# atmega128rf.net
KiCad netlist of a schematic drawn in Altium Designer
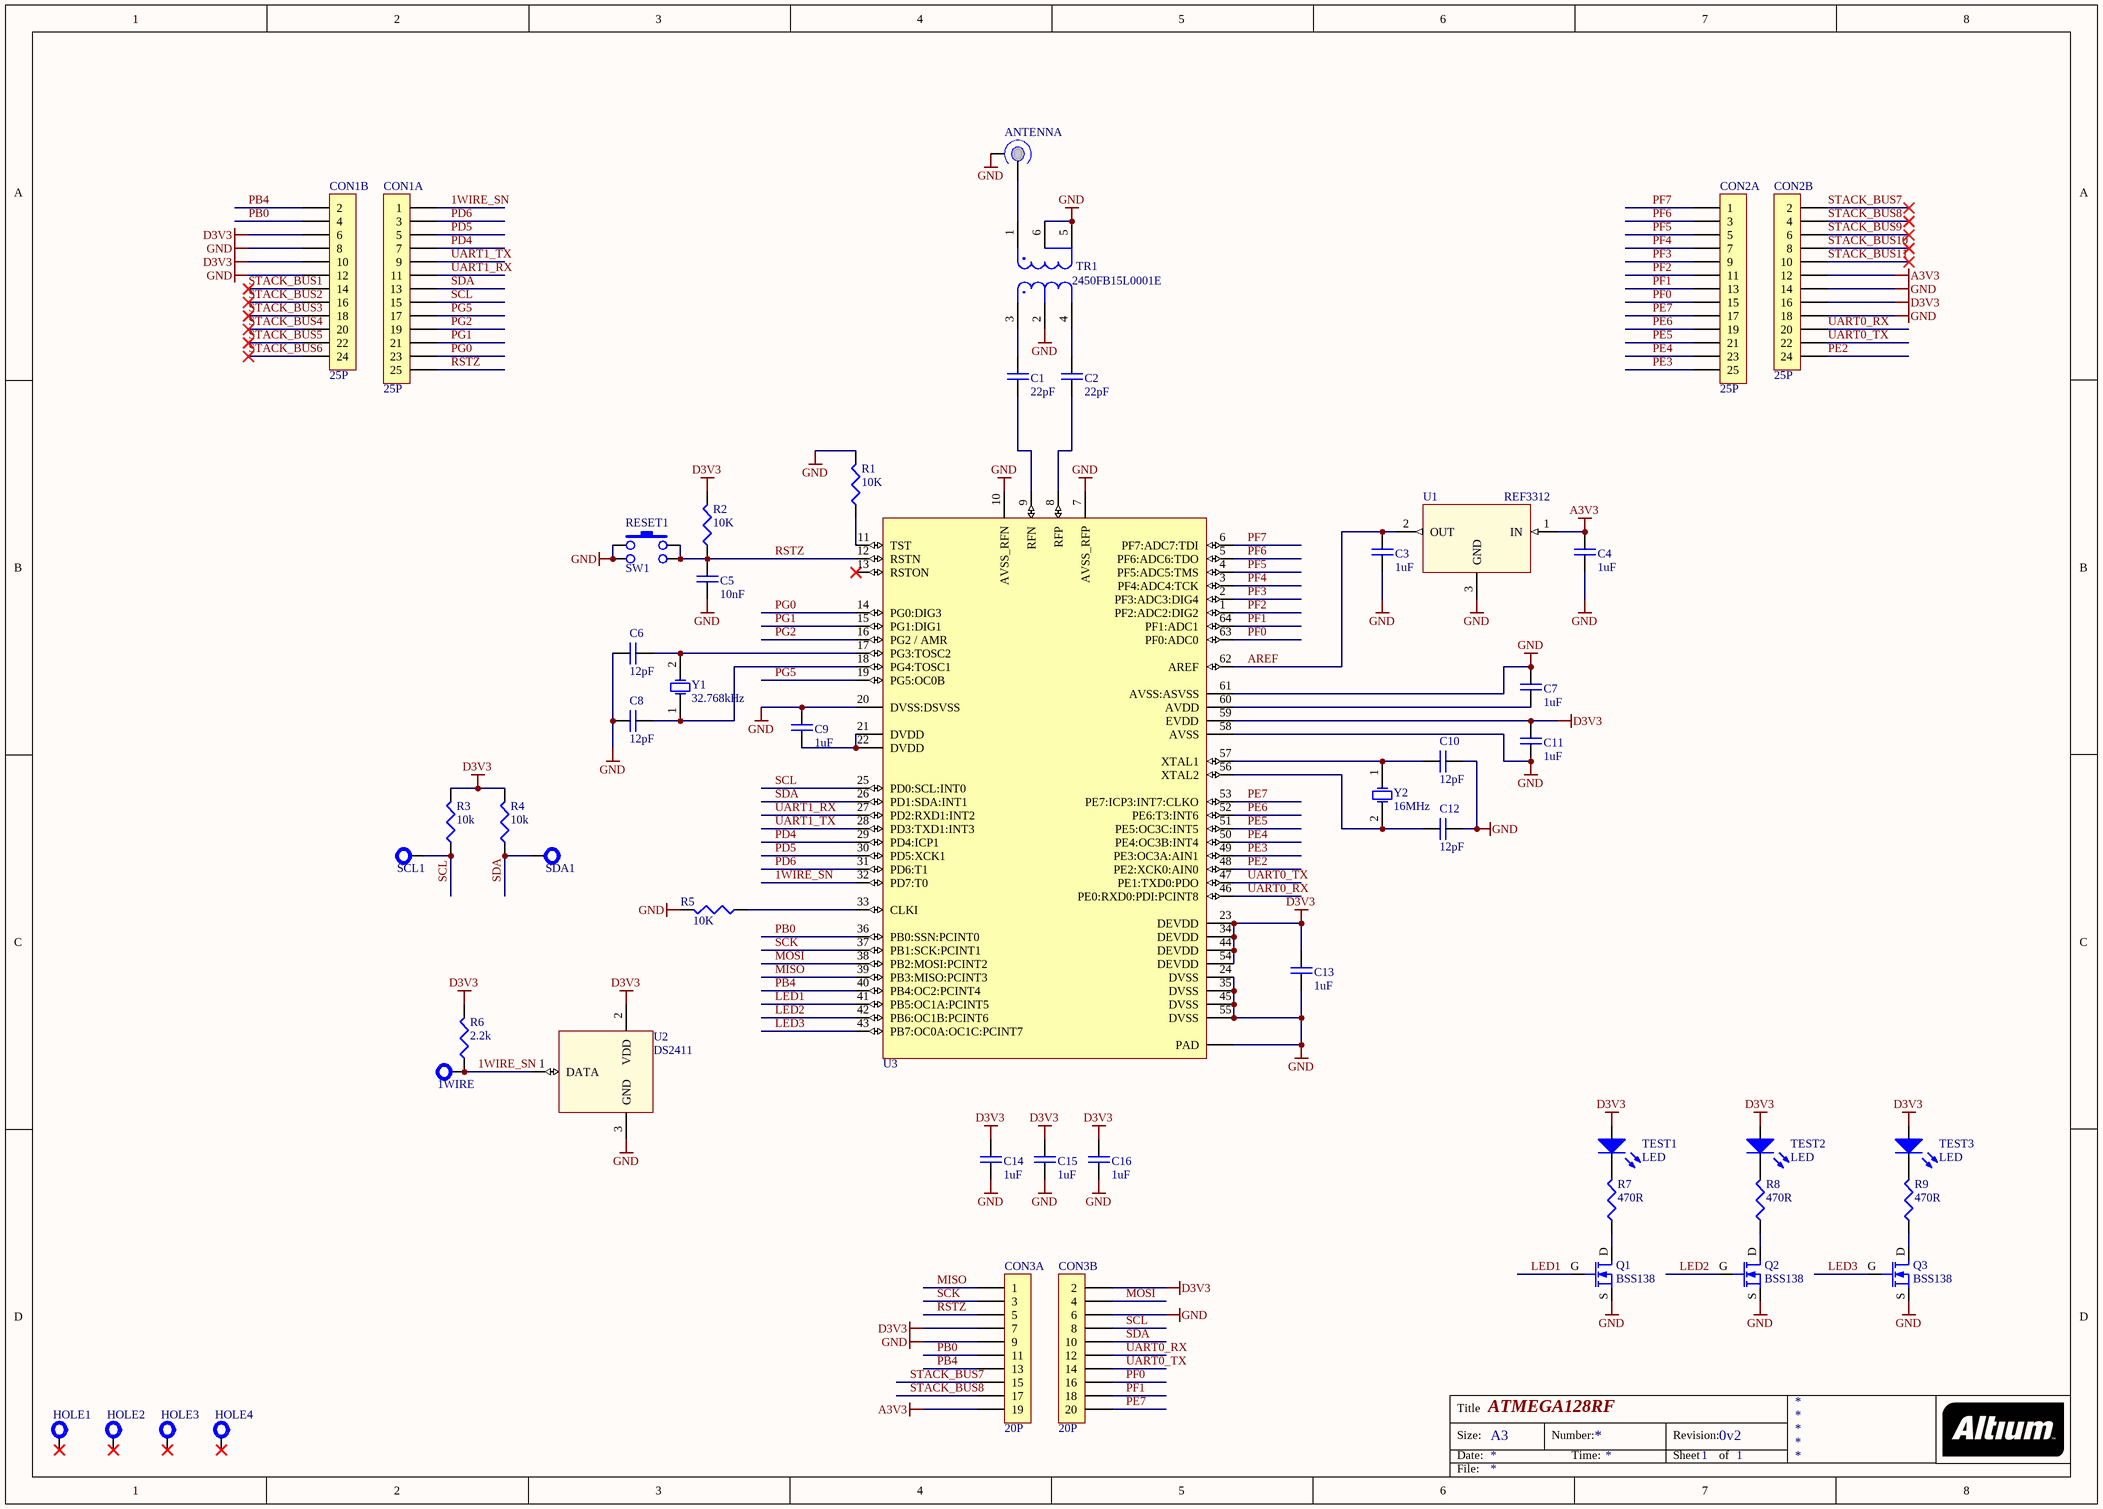
[diagram p0: atmega128rf.SchDoc]

(export (version "E")
  (design (tool "Eeschema 10.0.6"))
  (components
    (comp (ref "1WIRE")
      (value "Test Point")
      (footprint "TERMINAL")
      (description "Test/Probe Point")
      (fields (field (name "OWNER") "Nuno Brum"))
      (libsource (lib "Alcetronics_EM") (part "TEST-PROBE"))
    )
    (comp (ref "ANTENNA")
      (value "SMA")
      (footprint "SMA-JOHNSON-SCREW")
      (description "SMA to PCB - Coaxial connector")
      (fields (field (name "OWNER") "Nuno Brum"))
      (libsource (lib "Alcetronics_EM") (part "SMA"))
    )
    (comp (ref "C1")
      (value "22pF")
      (footprint "0402")
      (description "Capacitor")
      (fields (field (name "OWNER") "Nuno Brum"))
      (libsource (lib "Alcetronics_Devices") (part "CAP"))
    )
    (comp (ref "C2")
      (value "22pF")
      (footprint "0402")
      (description "Capacitor")
      (fields (field (name "OWNER") "Nuno Brum"))
      (libsource (lib "Alcetronics_Devices") (part "CAP"))
    )
    (comp (ref "C3")
      (value "1uF")
      (footprint "0603")
      (description "Capacitor")
      (fields (field (name "OWNER") "Nuno Brum"))
      (libsource (lib "Alcetronics_Devices") (part "CAP"))
    )
    (comp (ref "C4")
      (value "1uF")
      (footprint "0603")
      (description "Capacitor")
      (fields (field (name "OWNER") "Nuno Brum"))
      (libsource (lib "Alcetronics_Devices") (part "CAP"))
    )
    (comp (ref "C5")
      (value "10nF")
      (footprint "0603")
      (description "Capacitor")
      (fields (field (name "OWNER") "Nuno Brum"))
      (libsource (lib "Alcetronics_Devices") (part "CAP"))
    )
    (comp (ref "C6")
      (value "12pF")
      (footprint "0603")
      (description "Capacitor")
      (fields (field (name "OWNER") "Nuno Brum"))
      (libsource (lib "Alcetronics_Devices") (part "CAP"))
    )
    (comp (ref "C7")
      (value "1uF")
      (footprint "0603")
      (description "Capacitor")
      (fields (field (name "OWNER") "Nuno Brum"))
      (libsource (lib "Alcetronics_Devices") (part "CAP"))
    )
    (comp (ref "C8")
      (value "12pF")
      (footprint "0603")
      (description "Capacitor")
      (fields (field (name "OWNER") "Nuno Brum"))
      (libsource (lib "Alcetronics_Devices") (part "CAP"))
    )
    (comp (ref "C9")
      (value "1uF")
      (footprint "0603")
      (description "Capacitor")
      (fields (field (name "OWNER") "Nuno Brum"))
      (libsource (lib "Alcetronics_Devices") (part "CAP"))
    )
    (comp (ref "C10")
      (value "12pF")
      (footprint "0603")
      (description "Capacitor")
      (fields (field (name "OWNER") "Nuno Brum"))
      (libsource (lib "Alcetronics_Devices") (part "CAP"))
    )
    (comp (ref "C11")
      (value "1uF")
      (footprint "0603")
      (description "Capacitor")
      (fields (field (name "OWNER") "Nuno Brum"))
      (libsource (lib "Alcetronics_Devices") (part "CAP"))
    )
    (comp (ref "C12")
      (value "12pF")
      (footprint "0603")
      (description "Capacitor")
      (fields (field (name "OWNER") "Nuno Brum"))
      (libsource (lib "Alcetronics_Devices") (part "CAP"))
    )
    (comp (ref "C13")
      (value "1uF")
      (footprint "0603")
      (description "Capacitor")
      (fields (field (name "OWNER") "Nuno Brum"))
      (libsource (lib "Alcetronics_Devices") (part "CAP"))
    )
    (comp (ref "C14")
      (value "1uF")
      (footprint "0603")
      (description "Capacitor")
      (fields (field (name "OWNER") "Nuno Brum"))
      (libsource (lib "Alcetronics_Devices") (part "CAP"))
    )
    (comp (ref "C15")
      (value "1uF")
      (footprint "0603")
      (description "Capacitor")
      (fields (field (name "OWNER") "Nuno Brum"))
      (libsource (lib "Alcetronics_Devices") (part "CAP"))
    )
    (comp (ref "C16")
      (value "1uF")
      (footprint "0603")
      (description "Capacitor")
      (fields (field (name "OWNER") "Nuno Brum"))
      (libsource (lib "Alcetronics_Devices") (part "CAP"))
    )
    (comp (ref "CON1")
      (value "25P")
      (footprint "DF9-25-STACK")
      (description "Connector 25 Pins")
      (fields (field (name "OWNER") "Ricardo Rodrigues"))
      (libsource (lib "") (part "CON25_1"))
    )
    (comp (ref "CON2")
      (value "25P")
      (footprint "DF9-25-STACK")
      (description "Connector 25 Pins")
      (fields (field (name "OWNER") "Ricardo Rodrigues"))
      (libsource (lib "Alcetronics_EM") (part "CON25"))
    )
    (comp (ref "CON3")
      (value "20P")
      (footprint "IDC-20-EDGE")
      (description "Connector 20 Pins")
      (fields (field (name "OWNER") "Nuno Brum"))
      (libsource (lib "Alcetronics_EM") (part "CON20"))
    )
    (comp (ref "HOLE1")
      (value "HOLE")
      (footprint "NPTH-3MM")
      (description "PCB Fixation Hole M3")
      (fields (field (name "OWNER") "Nuno Brum"))
      (libsource (lib "Alcetronics_EM") (part "PCB HOLE"))
    )
    (comp (ref "HOLE2")
      (value "HOLE")
      (footprint "NPTH-3MM")
      (description "PCB Fixation Hole M3")
      (fields (field (name "OWNER") "Nuno Brum"))
      (libsource (lib "Alcetronics_EM") (part "PCB HOLE"))
    )
    (comp (ref "HOLE3")
      (value "HOLE")
      (footprint "NPTH-3MM")
      (description "PCB Fixation Hole M3")
      (fields (field (name "OWNER") "Nuno Brum"))
      (libsource (lib "Alcetronics_EM") (part "PCB HOLE"))
    )
    (comp (ref "HOLE4")
      (value "HOLE")
      (footprint "NPTH-3MM")
      (description "PCB Fixation Hole M3")
      (fields (field (name "OWNER") "Nuno Brum"))
      (libsource (lib "Alcetronics_EM") (part "PCB HOLE"))
    )
    (comp (ref "Q1")
      (value "BSS138")
      (footprint "SOT-23@GSD")
      (description "N-Channel Logic Level Enhancement Mode Field Effect Transistor")
      (fields (field (name "OWNER") "Nuno Brum"))
      (libsource (lib "Alcetronics_Devices") (part "MOSFET-N"))
    )
    (comp (ref "Q2")
      (value "BSS138")
      (footprint "SOT-23@GSD")
      (description "N-Channel Logic Level Enhancement Mode Field Effect Transistor")
      (fields (field (name "OWNER") "Nuno Brum"))
      (libsource (lib "Alcetronics_Devices") (part "MOSFET-N"))
    )
    (comp (ref "Q3")
      (value "BSS138")
      (footprint "SOT-23@GSD")
      (description "N-Channel Logic Level Enhancement Mode Field Effect Transistor")
      (fields (field (name "OWNER") "Nuno Brum"))
      (libsource (lib "Alcetronics_Devices") (part "MOSFET-N"))
    )
    (comp (ref "R1")
      (value "10K")
      (footprint "0603")
      (description "Resistor")
      (fields (field (name "OWNER") "Nuno Brum"))
      (libsource (lib "Alcetronics_Devices") (part "RES"))
    )
    (comp (ref "R2")
      (value "10K")
      (footprint "0603")
      (description "Resistor")
      (fields (field (name "OWNER") "Nuno Brum"))
      (libsource (lib "Alcetronics_Devices") (part "RES"))
    )
    (comp (ref "R3")
      (value "10k")
      (footprint "0603")
      (description "Resistor")
      (fields (field (name "OWNER") "Nuno Brum"))
      (libsource (lib "Alcetronics_Devices") (part "RES"))
    )
    (comp (ref "R4")
      (value "10k")
      (footprint "0603")
      (description "Resistor")
      (fields (field (name "OWNER") "Nuno Brum"))
      (libsource (lib "Alcetronics_Devices") (part "RES"))
    )
    (comp (ref "R5")
      (value "10K")
      (footprint "0603")
      (description "Resistor")
      (fields (field (name "OWNER") "Nuno Brum"))
      (libsource (lib "Alcetronics_Devices") (part "RES"))
    )
    (comp (ref "R6")
      (value "2.2k")
      (footprint "0603")
      (description "Resistor")
      (fields (field (name "OWNER") "Nuno Brum"))
      (libsource (lib "Alcetronics_Devices") (part "RES"))
    )
    (comp (ref "R7")
      (value "470R")
      (footprint "0603")
      (description "Resistor")
      (fields (field (name "OWNER") "Nuno Brum"))
      (libsource (lib "Alcetronics_Devices") (part "RES"))
    )
    (comp (ref "R8")
      (value "470R")
      (footprint "0603")
      (description "Resistor")
      (fields (field (name "OWNER") "Nuno Brum"))
      (libsource (lib "Alcetronics_Devices") (part "RES"))
    )
    (comp (ref "R9")
      (value "470R")
      (footprint "0603")
      (description "Resistor")
      (fields (field (name "OWNER") "Nuno Brum"))
      (libsource (lib "Alcetronics_Devices") (part "RES"))
    )
    (comp (ref "RESET1")
      (value "SW1")
      (footprint "MICROSWITCH")
      (description "Switch Push Button")
      (fields (field (name "OWNER") "Nuno Brum"))
      (libsource (lib "Alcetronics_EM") (part "SW1"))
    )
    (comp (ref "SCL1")
      (value "Test Point")
      (footprint "TERMINAL")
      (description "Test/Probe Point")
      (fields (field (name "OWNER") "Nuno Brum"))
      (libsource (lib "Alcetronics_EM") (part "TEST-PROBE"))
    )
    (comp (ref "SDA1")
      (value "Test Point")
      (footprint "TERMINAL")
      (description "Test/Probe Point")
      (fields (field (name "OWNER") "Nuno Brum"))
      (libsource (lib "Alcetronics_EM") (part "TEST-PROBE"))
    )
    (comp (ref "TEST1")
      (value "LED")
      (footprint "0805@DIODE")
      (description "Light emitting diode")
      (fields (field (name "OWNER") "Nuno Brum"))
      (libsource (lib "Alcetronics_Devices") (part "LED"))
    )
    (comp (ref "TEST2")
      (value "LED")
      (footprint "0805@DIODE")
      (description "Light emitting diode")
      (fields (field (name "OWNER") "Nuno Brum"))
      (libsource (lib "Alcetronics_Devices") (part "LED"))
    )
    (comp (ref "TEST3")
      (value "LED")
      (footprint "0805@DIODE")
      (description "Light emitting diode")
      (fields (field (name "OWNER") "Nuno Brum"))
      (libsource (lib "Alcetronics_Devices") (part "LED"))
    )
    (comp (ref "TR1")
      (value "2450FB15L0001E")
      (footprint "0805@BALUN")
      (description "FILTER BALUN ATMEL 2.45GHZ")
      (fields (field (name "OWNER") "Rui Rebelo"))
      (libsource (lib "Alcetronics_Devices") (part "2450FB15L0001E"))
    )
    (comp (ref "U1")
      (value "REF3312")
      (footprint "SOT-23")
      (description "Voltage Reference 1.25V, 30ppm/degC, 5mA")
      (libsource (lib "Alcetronics_IC") (part "REF3312"))
    )
    (comp (ref "U2")
      (value "DS2411")
      (footprint "SOT-23")
      (description "Silicon Serial Number")
      (libsource (lib "Alcetronics_IC") (part "DS2411"))
    )
    (comp (ref "U3")
      (value "ATmega128RFA1")
      (footprint "QFN-64@EP")
      (description "802.15.4 compliant AVR transceiver")
      (fields (field (name "VERIFIED BY") "vlarsen"))
      (libsource (lib "Alcetronics_IC") (part "ATmega128RFA1"))
    )
    (comp (ref "Y1")
      (value "32.768kHz")
      (footprint "XTAL-SMD-4.9x1.8")
      (description "Crystal Oscillator")
      (fields (field (name "PUBLISHER") "Altium Limited"))
      (libsource (lib "Alcetronics_Devices") (part "Crystal Oscillator"))
    )
    (comp (ref "Y2")
      (value "16MHz")
      (footprint "HC-49U")
      (description "Crystal Oscillator")
      (fields (field (name "PUBLISHER") "Altium Limited"))
      (libsource (lib "Alcetronics_Devices") (part "Crystal Oscillator"))
    )
  )
  (nets
    (net (code "1") (name "/1WIRE_SN") (class "Default")
      (node (ref "1WIRE") (pin "1") (pinfunction "TP_1") (pintype "passive"))
      (node (ref "CON1") (pin "1") (pinfunction "1_1") (pintype "passive"))
      (node (ref "R6") (pin "1") (pinfunction "1_1") (pintype "passive"))
      (node (ref "U2") (pin "1") (pinfunction "DATA_1") (pintype "bidirectional"))
      (node (ref "U3") (pin "32") (pinfunction "PD7:T0_32") (pintype "bidirectional"))
    )
    (net (code "2") (name "/AREF") (class "Default")
      (node (ref "C3") (pin "1") (pinfunction "1_1") (pintype "passive"))
      (node (ref "U1") (pin "2") (pinfunction "OUT_2") (pintype "output"))
      (node (ref "U3") (pin "62") (pinfunction "AREF_62") (pintype "bidirectional"))
    )
    (net (code "3") (name "/LED1") (class "Default")
      (node (ref "Q1") (pin "G") (pinfunction "G_G") (pintype "passive"))
      (node (ref "U3") (pin "41") (pinfunction "PB5:OC1A:PCINT5_41") (pintype "bidirectional"))
    )
    (net (code "4") (name "/LED2") (class "Default")
      (node (ref "Q2") (pin "G") (pinfunction "G_G") (pintype "passive"))
      (node (ref "U3") (pin "42") (pinfunction "PB6:OC1B:PCINT6_42") (pintype "bidirectional"))
    )
    (net (code "5") (name "/LED3") (class "Default")
      (node (ref "Q3") (pin "G") (pinfunction "G_G") (pintype "passive"))
      (node (ref "U3") (pin "43") (pinfunction "PB7:OC0A:OC1C:PCINT7_43") (pintype "bidirectional"))
    )
    (net (code "6") (name "/MISO") (class "Default")
      (node (ref "CON3") (pin "1") (pinfunction "1_1") (pintype "passive"))
      (node (ref "U3") (pin "39") (pinfunction "PB3:MISO:PCINT3_39") (pintype "bidirectional"))
    )
    (net (code "7") (name "/MOSI") (class "Default")
      (node (ref "CON3") (pin "4") (pinfunction "4_4") (pintype "passive"))
      (node (ref "U3") (pin "38") (pinfunction "PB2:MOSI:PCINT2_38") (pintype "bidirectional"))
    )
    (net (code "8") (name "/PB0") (class "Default")
      (node (ref "CON1") (pin "4") (pinfunction "4_4") (pintype "passive"))
      (node (ref "CON3") (pin "11") (pinfunction "11_11") (pintype "passive"))
      (node (ref "U3") (pin "36") (pinfunction "PB0:SSN:PCINT0_36") (pintype "bidirectional"))
    )
    (net (code "9") (name "/PB4") (class "Default")
      (node (ref "CON1") (pin "2") (pinfunction "2_2") (pintype "passive"))
      (node (ref "CON3") (pin "13") (pinfunction "13_13") (pintype "passive"))
      (node (ref "U3") (pin "40") (pinfunction "PB4:OC2:PCINT4_40") (pintype "bidirectional"))
    )
    (net (code "10") (name "/PD4") (class "Default")
      (node (ref "CON1") (pin "7") (pinfunction "7_7") (pintype "passive"))
      (node (ref "U3") (pin "29") (pinfunction "PD4:ICP1_29") (pintype "bidirectional"))
    )
    (net (code "11") (name "/PD5") (class "Default")
      (node (ref "CON1") (pin "5") (pinfunction "5_5") (pintype "passive"))
      (node (ref "U3") (pin "30") (pinfunction "PD5:XCK1_30") (pintype "bidirectional"))
    )
    (net (code "12") (name "/PD6") (class "Default")
      (node (ref "CON1") (pin "3") (pinfunction "3_3") (pintype "passive"))
      (node (ref "U3") (pin "31") (pinfunction "PD6:T1_31") (pintype "bidirectional"))
    )
    (net (code "13") (name "/PE2") (class "Default")
      (node (ref "CON2") (pin "24") (pinfunction "24_24") (pintype "passive"))
      (node (ref "U3") (pin "48") (pinfunction "PE2:XCK0:AIN0_48") (pintype "bidirectional"))
    )
    (net (code "14") (name "/PE3") (class "Default")
      (node (ref "CON2") (pin "25") (pinfunction "25_25") (pintype "passive"))
      (node (ref "U3") (pin "49") (pinfunction "PE3:OC3A:AIN1_49") (pintype "bidirectional"))
    )
    (net (code "15") (name "/PE4") (class "Default")
      (node (ref "CON2") (pin "23") (pinfunction "23_23") (pintype "passive"))
      (node (ref "U3") (pin "50") (pinfunction "PE4:OC3B:INT4_50") (pintype "bidirectional"))
    )
    (net (code "16") (name "/PE5") (class "Default")
      (node (ref "CON2") (pin "21") (pinfunction "21_21") (pintype "passive"))
      (node (ref "U3") (pin "51") (pinfunction "PE5:OC3C:INT5_51") (pintype "bidirectional"))
    )
    (net (code "17") (name "/PE6") (class "Default")
      (node (ref "CON2") (pin "19") (pinfunction "19_19") (pintype "passive"))
      (node (ref "U3") (pin "52") (pinfunction "PE6:T3:INT6_52") (pintype "bidirectional"))
    )
    (net (code "18") (name "/PE7") (class "Default")
      (node (ref "CON2") (pin "17") (pinfunction "17_17") (pintype "passive"))
      (node (ref "CON3") (pin "20") (pinfunction "20_20") (pintype "passive"))
      (node (ref "U3") (pin "53") (pinfunction "PE7:ICP3:INT7:CLKO_53") (pintype "bidirectional"))
    )
    (net (code "19") (name "/PF0") (class "Default")
      (node (ref "CON2") (pin "15") (pinfunction "15_15") (pintype "passive"))
      (node (ref "CON3") (pin "16") (pinfunction "16_16") (pintype "passive"))
      (node (ref "U3") (pin "63") (pinfunction "PF0:ADC0_63") (pintype "bidirectional"))
    )
    (net (code "20") (name "/PF1") (class "Default")
      (node (ref "CON2") (pin "13") (pinfunction "13_13") (pintype "passive"))
      (node (ref "CON3") (pin "18") (pinfunction "18_18") (pintype "passive"))
      (node (ref "U3") (pin "64") (pinfunction "PF1:ADC1_64") (pintype "bidirectional"))
    )
    (net (code "21") (name "/PF2") (class "Default")
      (node (ref "CON2") (pin "11") (pinfunction "11_11") (pintype "passive"))
      (node (ref "U3") (pin "1") (pinfunction "PF2:ADC2:DIG2_1") (pintype "bidirectional"))
    )
    (net (code "22") (name "/PF3") (class "Default")
      (node (ref "CON2") (pin "9") (pinfunction "9_9") (pintype "passive"))
      (node (ref "U3") (pin "2") (pinfunction "PF3:ADC3:DIG4_2") (pintype "bidirectional"))
    )
    (net (code "23") (name "/PF4") (class "Default")
      (node (ref "CON2") (pin "7") (pinfunction "7_7") (pintype "passive"))
      (node (ref "U3") (pin "3") (pinfunction "PF4:ADC4:TCK_3") (pintype "bidirectional"))
    )
    (net (code "24") (name "/PF5") (class "Default")
      (node (ref "CON2") (pin "5") (pinfunction "5_5") (pintype "passive"))
      (node (ref "U3") (pin "4") (pinfunction "PF5:ADC5:TMS_4") (pintype "bidirectional"))
    )
    (net (code "25") (name "/PF6") (class "Default")
      (node (ref "CON2") (pin "3") (pinfunction "3_3") (pintype "passive"))
      (node (ref "U3") (pin "5") (pinfunction "PF6:ADC6:TDO_5") (pintype "bidirectional"))
    )
    (net (code "26") (name "/PF7") (class "Default")
      (node (ref "CON2") (pin "1") (pinfunction "1_1") (pintype "passive"))
      (node (ref "U3") (pin "6") (pinfunction "PF7:ADC7:TDI_6") (pintype "bidirectional"))
    )
    (net (code "27") (name "/PG0") (class "Default")
      (node (ref "CON1") (pin "23") (pinfunction "23_23") (pintype "passive"))
      (node (ref "U3") (pin "14") (pinfunction "PG0:DIG3_14") (pintype "bidirectional"))
    )
    (net (code "28") (name "/PG1") (class "Default")
      (node (ref "CON1") (pin "21") (pinfunction "21_21") (pintype "passive"))
      (node (ref "U3") (pin "15") (pinfunction "PG1:DIG1_15") (pintype "bidirectional"))
    )
    (net (code "29") (name "/PG2") (class "Default")
      (node (ref "CON1") (pin "19") (pinfunction "19_19") (pintype "passive"))
      (node (ref "U3") (pin "16") (pinfunction "PG2_/_AMR_16") (pintype "bidirectional"))
    )
    (net (code "30") (name "/PG5") (class "Default")
      (node (ref "CON1") (pin "17") (pinfunction "17_17") (pintype "passive"))
      (node (ref "U3") (pin "19") (pinfunction "PG5:OC0B_19") (pintype "bidirectional"))
    )
    (net (code "31") (name "/RSTZ") (class "Default")
      (node (ref "C5") (pin "1") (pinfunction "1_1") (pintype "passive"))
      (node (ref "CON1") (pin "25") (pinfunction "25_25") (pintype "passive"))
      (node (ref "CON3") (pin "5") (pinfunction "5_5") (pintype "passive"))
      (node (ref "R2") (pin "1") (pinfunction "1_1") (pintype "passive"))
      (node (ref "RESET1") (pin "2") (pinfunction "2_2") (pintype "passive"))
      (node (ref "RESET1") (pin "4") (pinfunction "4_4") (pintype "passive"))
      (node (ref "U3") (pin "12") (pinfunction "RSTN_12") (pintype "bidirectional"))
    )
    (net (code "32") (name "/SCK") (class "Default")
      (node (ref "CON3") (pin "3") (pinfunction "3_3") (pintype "passive"))
      (node (ref "U3") (pin "37") (pinfunction "PB1:SCK:PCINT1_37") (pintype "bidirectional"))
    )
    (net (code "33") (name "/SCL") (class "Default")
      (node (ref "CON1") (pin "15") (pinfunction "15_15") (pintype "passive"))
      (node (ref "CON3") (pin "8") (pinfunction "8_8") (pintype "passive"))
      (node (ref "R3") (pin "1") (pinfunction "1_1") (pintype "passive"))
      (node (ref "SCL1") (pin "1") (pinfunction "TP_1") (pintype "passive"))
      (node (ref "U3") (pin "25") (pinfunction "PD0:SCL:INT0_25") (pintype "bidirectional"))
    )
    (net (code "34") (name "/SDA") (class "Default")
      (node (ref "CON1") (pin "13") (pinfunction "13_13") (pintype "passive"))
      (node (ref "CON3") (pin "10") (pinfunction "10_10") (pintype "passive"))
      (node (ref "R4") (pin "1") (pinfunction "1_1") (pintype "passive"))
      (node (ref "SDA1") (pin "1") (pinfunction "TP_1") (pintype "passive"))
      (node (ref "U3") (pin "26") (pinfunction "PD1:SDA:INT1_26") (pintype "bidirectional"))
    )
    (net (code "35") (name "/STACK_BUS1") (class "Default")
      (node (ref "CON1") (pin "14") (pinfunction "14_14") (pintype "passive+no_connect"))
    )
    (net (code "36") (name "/STACK_BUS2") (class "Default")
      (node (ref "CON1") (pin "16") (pinfunction "16_16") (pintype "passive+no_connect"))
    )
    (net (code "37") (name "/STACK_BUS3") (class "Default")
      (node (ref "CON1") (pin "18") (pinfunction "18_18") (pintype "passive+no_connect"))
    )
    (net (code "38") (name "/STACK_BUS4") (class "Default")
      (node (ref "CON1") (pin "20") (pinfunction "20_20") (pintype "passive+no_connect"))
    )
    (net (code "39") (name "/STACK_BUS5") (class "Default")
      (node (ref "CON1") (pin "22") (pinfunction "22_22") (pintype "passive+no_connect"))
    )
    (net (code "40") (name "/STACK_BUS6") (class "Default")
      (node (ref "CON1") (pin "24") (pinfunction "24_24") (pintype "passive+no_connect"))
    )
    (net (code "41") (name "/STACK_BUS7") (class "Default")
      (node (ref "CON2") (pin "2") (pinfunction "2_2") (pintype "passive"))
      (node (ref "CON3") (pin "15") (pinfunction "15_15") (pintype "passive"))
    )
    (net (code "42") (name "/STACK_BUS8") (class "Default")
      (node (ref "CON2") (pin "4") (pinfunction "4_4") (pintype "passive"))
      (node (ref "CON3") (pin "17") (pinfunction "17_17") (pintype "passive"))
    )
    (net (code "43") (name "/STACK_BUS9") (class "Default")
      (node (ref "CON2") (pin "6") (pinfunction "6_6") (pintype "passive+no_connect"))
    )
    (net (code "44") (name "/STACK_BUS10") (class "Default")
      (node (ref "CON2") (pin "8") (pinfunction "8_8") (pintype "passive+no_connect"))
    )
    (net (code "45") (name "/STACK_BUS11") (class "Default")
      (node (ref "CON2") (pin "10") (pinfunction "10_10") (pintype "passive+no_connect"))
    )
    (net (code "46") (name "/UART0_RX") (class "Default")
      (node (ref "CON2") (pin "20") (pinfunction "20_20") (pintype "passive"))
      (node (ref "CON3") (pin "12") (pinfunction "12_12") (pintype "passive"))
      (node (ref "U3") (pin "46") (pinfunction "PE0:RXD0:PDI:PCINT8_46") (pintype "bidirectional"))
    )
    (net (code "47") (name "/UART0_TX") (class "Default")
      (node (ref "CON2") (pin "22") (pinfunction "22_22") (pintype "passive"))
      (node (ref "CON3") (pin "14") (pinfunction "14_14") (pintype "passive"))
      (node (ref "U3") (pin "47") (pinfunction "PE1:TXD0:PDO_47") (pintype "bidirectional"))
    )
    (net (code "48") (name "/UART1_RX") (class "Default")
      (node (ref "CON1") (pin "11") (pinfunction "11_11") (pintype "passive"))
      (node (ref "U3") (pin "27") (pinfunction "PD2:RXD1:INT2_27") (pintype "bidirectional"))
    )
    (net (code "49") (name "/UART1_TX") (class "Default")
      (node (ref "CON1") (pin "9") (pinfunction "9_9") (pintype "passive"))
      (node (ref "U3") (pin "28") (pinfunction "PD3:TXD1:INT3_28") (pintype "bidirectional"))
    )
    (net (code "50") (name "A3V3") (class "Default")
      (node (ref "C4") (pin "1") (pinfunction "1_1") (pintype "passive"))
      (node (ref "CON2") (pin "12") (pinfunction "12_12") (pintype "passive"))
      (node (ref "CON3") (pin "19") (pinfunction "19_19") (pintype "passive"))
      (node (ref "U1") (pin "1") (pinfunction "IN_1") (pintype "input"))
    )
    (net (code "51") (name "D3V3") (class "Default")
      (node (ref "C11") (pin "2") (pinfunction "2_2") (pintype "passive"))
      (node (ref "C13") (pin "2") (pinfunction "2_2") (pintype "passive"))
      (node (ref "C14") (pin "2") (pinfunction "2_2") (pintype "passive"))
      (node (ref "C15") (pin "2") (pinfunction "2_2") (pintype "passive"))
      (node (ref "C16") (pin "2") (pinfunction "2_2") (pintype "passive"))
      (node (ref "CON1") (pin "10") (pinfunction "10_10") (pintype "passive"))
      (node (ref "CON1") (pin "6") (pinfunction "6_6") (pintype "passive"))
      (node (ref "CON2") (pin "16") (pinfunction "16_16") (pintype "passive"))
      (node (ref "CON3") (pin "2") (pinfunction "2_2") (pintype "passive"))
      (node (ref "CON3") (pin "7") (pinfunction "7_7") (pintype "passive"))
      (node (ref "R2") (pin "2") (pinfunction "2_2") (pintype "passive"))
      (node (ref "R3") (pin "2") (pinfunction "2_2") (pintype "passive"))
      (node (ref "R4") (pin "2") (pinfunction "2_2") (pintype "passive"))
      (node (ref "R6") (pin "2") (pinfunction "2_2") (pintype "passive"))
      (node (ref "TEST1") (pin "A") (pinfunction "A_A") (pintype "passive"))
      (node (ref "TEST2") (pin "A") (pinfunction "A_A") (pintype "passive"))
      (node (ref "TEST3") (pin "A") (pinfunction "A_A") (pintype "passive"))
      (node (ref "U2") (pin "2") (pinfunction "VDD_2") (pintype "power_in"))
      (node (ref "U3") (pin "23") (pinfunction "DEVDD_23") (pintype "power_in"))
      (node (ref "U3") (pin "34") (pinfunction "DEVDD_34") (pintype "power_in"))
      (node (ref "U3") (pin "44") (pinfunction "DEVDD_44") (pintype "power_in"))
      (node (ref "U3") (pin "54") (pinfunction "DEVDD_54") (pintype "power_in"))
      (node (ref "U3") (pin "59") (pinfunction "EVDD_59") (pintype "power_in"))
    )
    (net (code "52") (name "GND") (class "Default")
      (node (ref "ANTENNA") (pin "2") (pinfunction "GND_2") (pintype "passive"))
      (node (ref "C10") (pin "2") (pinfunction "2_2") (pintype "passive"))
      (node (ref "C11") (pin "1") (pinfunction "1_1") (pintype "passive"))
      (node (ref "C12") (pin "2") (pinfunction "2_2") (pintype "passive"))
      (node (ref "C13") (pin "1") (pinfunction "1_1") (pintype "passive"))
      (node (ref "C14") (pin "1") (pinfunction "1_1") (pintype "passive"))
      (node (ref "C15") (pin "1") (pinfunction "1_1") (pintype "passive"))
      (node (ref "C16") (pin "1") (pinfunction "1_1") (pintype "passive"))
      (node (ref "C3") (pin "2") (pinfunction "2_2") (pintype "passive"))
      (node (ref "C4") (pin "2") (pinfunction "2_2") (pintype "passive"))
      (node (ref "C5") (pin "2") (pinfunction "2_2") (pintype "passive"))
      (node (ref "C6") (pin "1") (pinfunction "1_1") (pintype "passive"))
      (node (ref "C7") (pin "2") (pinfunction "2_2") (pintype "passive"))
      (node (ref "C8") (pin "1") (pinfunction "1_1") (pintype "passive"))
      (node (ref "C9") (pin "2") (pinfunction "2_2") (pintype "passive"))
      (node (ref "CON1") (pin "12") (pinfunction "12_12") (pintype "passive"))
      (node (ref "CON1") (pin "8") (pinfunction "8_8") (pintype "passive"))
      (node (ref "CON2") (pin "14") (pinfunction "14_14") (pintype "passive"))
      (node (ref "CON2") (pin "18") (pinfunction "18_18") (pintype "passive"))
      (node (ref "CON3") (pin "6") (pinfunction "6_6") (pintype "passive"))
      (node (ref "CON3") (pin "9") (pinfunction "9_9") (pintype "passive"))
      (node (ref "Q1") (pin "S") (pinfunction "S_S") (pintype "passive"))
      (node (ref "Q2") (pin "S") (pinfunction "S_S") (pintype "passive"))
      (node (ref "Q3") (pin "S") (pinfunction "S_S") (pintype "passive"))
      (node (ref "R1") (pin "2") (pinfunction "2_2") (pintype "passive"))
      (node (ref "R5") (pin "2") (pinfunction "2_2") (pintype "passive"))
      (node (ref "RESET1") (pin "1") (pinfunction "1_1") (pintype "passive"))
      (node (ref "RESET1") (pin "3") (pinfunction "3_3") (pintype "passive"))
      (node (ref "TR1") (pin "2") (pinfunction "DC_Feed_+_RF_GND_2") (pintype "passive"))
      (node (ref "TR1") (pin "5") (pinfunction "Ground_5") (pintype "passive"))
      (node (ref "TR1") (pin "6") (pinfunction "Ground_6") (pintype "passive"))
      (node (ref "U1") (pin "3") (pinfunction "GND_3") (pintype "power_in"))
      (node (ref "U2") (pin "3") (pinfunction "GND_3") (pintype "power_in"))
      (node (ref "U3") (pin "10") (pinfunction "AVSS_RFN_10") (pintype "power_in"))
      (node (ref "U3") (pin "20") (pinfunction "DVSS:DSVSS_20") (pintype "power_in"))
      (node (ref "U3") (pin "24") (pinfunction "DVSS_24") (pintype "power_in"))
      (node (ref "U3") (pin "35") (pinfunction "DVSS_35") (pintype "power_in"))
      (node (ref "U3") (pin "45") (pinfunction "DVSS_45") (pintype "power_in"))
      (node (ref "U3") (pin "55") (pinfunction "DVSS_55") (pintype "power_in"))
      (node (ref "U3") (pin "58") (pinfunction "AVSS_58") (pintype "power_in"))
      (node (ref "U3") (pin "61") (pinfunction "AVSS:ASVSS_61") (pintype "power_in"))
      (node (ref "U3") (pin "7") (pinfunction "AVSS_RFP_7") (pintype "power_in"))
      (node (ref "U3") (pin "PAD") (pinfunction "PAD_PAD") (pintype "power_in"))
    )
    (net (code "53") (name "Net-(ANTENNA-SIG)") (class "Default")
      (node (ref "ANTENNA") (pin "1") (pinfunction "SIG_1") (pintype "passive"))
      (node (ref "TR1") (pin "1") (pinfunction "Unbalanced_Port_1") (pintype "passive"))
    )
    (net (code "54") (name "Net-(C1-Pad2)") (class "Default")
      (node (ref "C1") (pin "2") (pinfunction "2_2") (pintype "passive"))
      (node (ref "TR1") (pin "3") (pinfunction "Balanced_Port_3") (pintype "passive"))
    )
    (net (code "55") (name "Net-(C2-Pad2)") (class "Default")
      (node (ref "C2") (pin "2") (pinfunction "2_2") (pintype "passive"))
      (node (ref "TR1") (pin "4") (pinfunction "Balanced_Port_4") (pintype "passive"))
    )
    (net (code "56") (name "Net-(C9-Pad1)") (class "Default")
      (node (ref "C9") (pin "1") (pinfunction "1_1") (pintype "passive"))
      (node (ref "U3") (pin "21") (pinfunction "DVDD_21") (pintype "power_in"))
      (node (ref "U3") (pin "22") (pinfunction "DVDD_22") (pintype "power_in"))
    )
    (net (code "57") (name "Net-(Q1-PadD)") (class "Default")
      (node (ref "Q1") (pin "D") (pinfunction "D_D") (pintype "passive"))
      (node (ref "R7") (pin "1") (pinfunction "1_1") (pintype "passive"))
    )
    (net (code "58") (name "Net-(Q2-PadD)") (class "Default")
      (node (ref "Q2") (pin "D") (pinfunction "D_D") (pintype "passive"))
      (node (ref "R8") (pin "1") (pinfunction "1_1") (pintype "passive"))
    )
    (net (code "59") (name "Net-(Q3-PadD)") (class "Default")
      (node (ref "Q3") (pin "D") (pinfunction "D_D") (pintype "passive"))
      (node (ref "R9") (pin "1") (pinfunction "1_1") (pintype "passive"))
    )
    (net (code "60") (name "Net-(R7-Pad2)") (class "Default")
      (node (ref "R7") (pin "2") (pinfunction "2_2") (pintype "passive"))
      (node (ref "TEST1") (pin "K") (pinfunction "K_K") (pintype "passive"))
    )
    (net (code "61") (name "Net-(R8-Pad2)") (class "Default")
      (node (ref "R8") (pin "2") (pinfunction "2_2") (pintype "passive"))
      (node (ref "TEST2") (pin "K") (pinfunction "K_K") (pintype "passive"))
    )
    (net (code "62") (name "Net-(R9-Pad2)") (class "Default")
      (node (ref "R9") (pin "2") (pinfunction "2_2") (pintype "passive"))
      (node (ref "TEST3") (pin "K") (pinfunction "K_K") (pintype "passive"))
    )
    (net (code "63") (name "Net-(U3-AVDD)") (class "Default")
      (node (ref "C7") (pin "1") (pinfunction "1_1") (pintype "passive"))
      (node (ref "U3") (pin "60") (pinfunction "AVDD_60") (pintype "power_in"))
    )
    (net (code "64") (name "Net-(U3-CLKI)") (class "Default")
      (node (ref "R5") (pin "1") (pinfunction "1_1") (pintype "passive"))
      (node (ref "U3") (pin "33") (pinfunction "CLKI_33") (pintype "bidirectional"))
    )
    (net (code "65") (name "Net-(U3-PG3:TOSC2)") (class "Default")
      (node (ref "C6") (pin "2") (pinfunction "2_2") (pintype "passive"))
      (node (ref "U3") (pin "17") (pinfunction "PG3:TOSC2_17") (pintype "bidirectional"))
      (node (ref "Y1") (pin "2") (pinfunction "OSC2_2") (pintype "passive"))
    )
    (net (code "66") (name "Net-(U3-PG4:TOSC1)") (class "Default")
      (node (ref "C8") (pin "2") (pinfunction "2_2") (pintype "passive"))
      (node (ref "U3") (pin "18") (pinfunction "PG4:TOSC1_18") (pintype "bidirectional"))
      (node (ref "Y1") (pin "1") (pinfunction "OSC1_1") (pintype "passive"))
    )
    (net (code "67") (name "Net-(U3-RFN)") (class "Default")
      (node (ref "C1") (pin "1") (pinfunction "1_1") (pintype "passive"))
      (node (ref "U3") (pin "9") (pinfunction "RFN_9") (pintype "bidirectional"))
    )
    (net (code "68") (name "Net-(U3-RFP)") (class "Default")
      (node (ref "C2") (pin "1") (pinfunction "1_1") (pintype "passive"))
      (node (ref "U3") (pin "8") (pinfunction "RFP_8") (pintype "bidirectional"))
    )
    (net (code "69") (name "Net-(U3-TST)") (class "Default")
      (node (ref "R1") (pin "1") (pinfunction "1_1") (pintype "passive"))
      (node (ref "U3") (pin "11") (pinfunction "TST_11") (pintype "bidirectional"))
    )
    (net (code "70") (name "Net-(U3-XTAL1)") (class "Default")
      (node (ref "C10") (pin "1") (pinfunction "1_1") (pintype "passive"))
      (node (ref "U3") (pin "57") (pinfunction "XTAL1_57") (pintype "bidirectional"))
      (node (ref "Y2") (pin "1") (pinfunction "OSC1_1") (pintype "passive"))
    )
    (net (code "71") (name "Net-(U3-XTAL2)") (class "Default")
      (node (ref "C12") (pin "1") (pinfunction "1_1") (pintype "passive"))
      (node (ref "U3") (pin "56") (pinfunction "XTAL2_56") (pintype "bidirectional"))
      (node (ref "Y2") (pin "2") (pinfunction "OSC2_2") (pintype "passive"))
    )
    (net (code "72") (name "unconnected-(HOLE1-TP-Pad1)") (class "Default")
      (node (ref "HOLE1") (pin "1") (pinfunction "TP_1") (pintype "passive+no_connect"))
    )
    (net (code "73") (name "unconnected-(HOLE2-TP-Pad1)") (class "Default")
      (node (ref "HOLE2") (pin "1") (pinfunction "TP_1") (pintype "passive+no_connect"))
    )
    (net (code "74") (name "unconnected-(HOLE3-TP-Pad1)") (class "Default")
      (node (ref "HOLE3") (pin "1") (pinfunction "TP_1") (pintype "passive+no_connect"))
    )
    (net (code "75") (name "unconnected-(HOLE4-TP-Pad1)") (class "Default")
      (node (ref "HOLE4") (pin "1") (pinfunction "TP_1") (pintype "passive+no_connect"))
    )
    (net (code "76") (name "unconnected-(U3-RSTON-Pad13)") (class "Default")
      (node (ref "U3") (pin "13") (pinfunction "RSTON_13") (pintype "bidirectional+no_connect"))
    )
  )
)
